# ProDoc_TP4056_2025-08-24.net
KiCad netlist of a schematic drawn in EasyEDA Pro
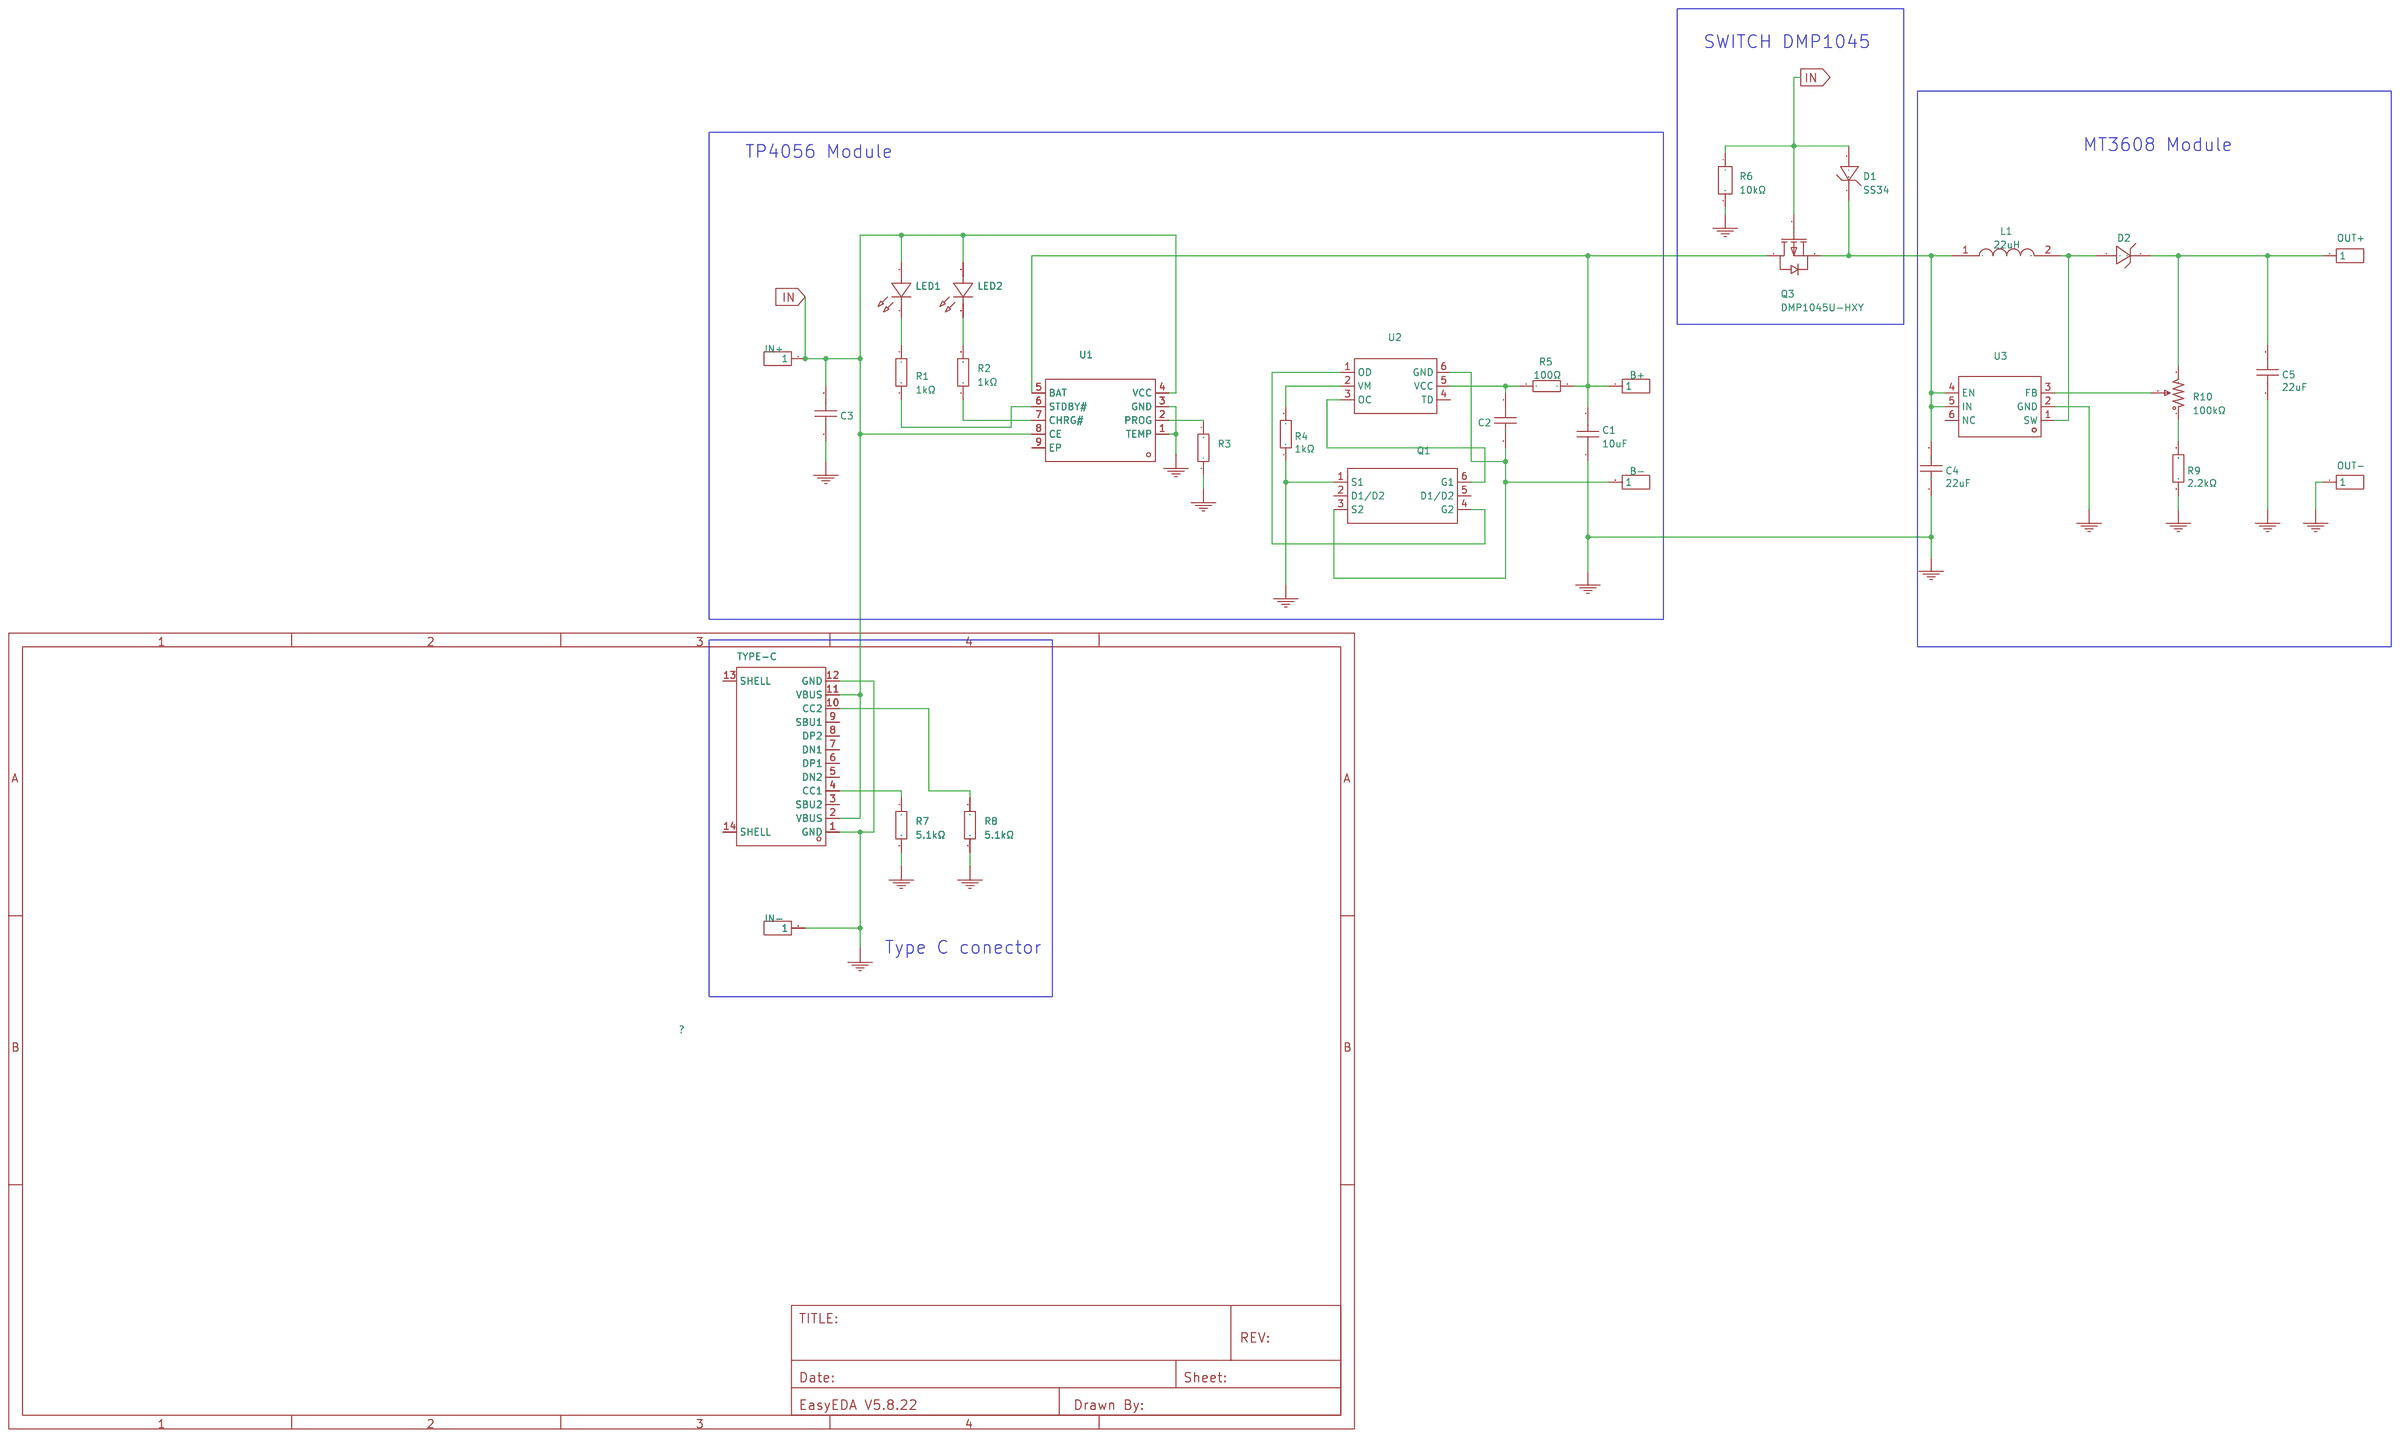
[diagram p0: schematic sheet]

(export (version "E")
  (design (tool "Eeschema 10.0.6"))
  (components
    (comp (ref "B+")
      (value "Header-Male-2.54_1x1")
      (footprint "easyedapro:HDR-1X1/2.54")
      (fields (field (name "Manufacturer") "ReliaPro"))
      (libsource (lib "") (part "Header-Male-2.54_1x1_1"))
    )
    (comp (ref "B-")
      (value "Header-Male-2.54_1x1")
      (footprint "easyedapro:HDR-1X1/2.54")
      (fields (field (name "Manufacturer") "ReliaPro"))
      (libsource (lib "") (part "Header-Male-2.54_1x1_1"))
    )
    (comp (ref "C1")
      (value "10uF")
      (footprint "easyedapro:C0603")
      (description "Capacitance:10uF Tolerance:±10% Tolerance:±10% Voltage Rating:- Temperature Coefficient:X5R")
      (fields (field (name "Manufacturer Part") "0603X106K100CT") (field (name "Manufacturer") "Walsin(华新科)"))
      (libsource (lib "easyedapro") (part "0603X106K100CT"))
    )
    (comp (ref "C2")
      (value "100nF")
      (footprint "easyedapro:C0603")
      (fields
        (field (name "Manufacturer Part") "CC0603KRX7R9BB104")
        (field (name "Manufacturer") "YAGEO(国巨)")
      )
      (libsource (lib "easyedapro") (part "CC0603KRX7R9BB104"))
    )
    (comp (ref "C3")
      (value "100nF")
      (footprint "easyedapro:C0603")
      (fields
        (field (name "Manufacturer Part") "CC0603KRX7R9BB104")
        (field (name "Manufacturer") "YAGEO(国巨)")
      )
      (libsource (lib "easyedapro") (part "CC0603KRX7R9BB104"))
    )
    (comp (ref "C4")
      (value "22uF")
      (footprint "easyedapro:C1206")
      (description "Capacitance:22uF Voltage Rating:25V Temperature Coefficient:-")
      (fields
        (field (name "Manufacturer Part") "C1206X6S226M250NT")
        (field (name "Manufacturer") "SANYEAR(叁叶源)")
      )
      (libsource (lib "easyedapro") (part "C1206X6S226M250NT"))
    )
    (comp (ref "C5")
      (value "22uF")
      (footprint "easyedapro:C1206")
      (description "Capacitance:22uF Voltage Rating:25V Temperature Coefficient:-")
      (fields
        (field (name "Manufacturer Part") "C1206X6S226M250NT")
        (field (name "Manufacturer") "SANYEAR(叁叶源)")
      )
      (libsource (lib "easyedapro") (part "C1206X6S226M250NT"))
    )
    (comp (ref "D1")
      (value "SS34")
      (footprint "easyedapro:SMB_L4.3-W3.6-LS5.3-RD")
      (fields (field (name "Manufacturer") "TECH PUBLIC(台舟)"))
      (libsource (lib "easyedapro") (part "SS34_C3040628"))
    )
    (comp (ref "D2")
      (value "SS34")
      (footprint "easyedapro:SMB_L4.3-W3.6-LS5.3-RD")
      (fields (field (name "Manufacturer") "TECH PUBLIC(台舟)"))
      (libsource (lib "easyedapro") (part "SS34_C3040628"))
    )
    (comp (ref "IN+")
      (value "Header-Male-2.54_1x1")
      (footprint "easyedapro:HDR-1X1/2.54")
      (fields (field (name "Manufacturer") "ReliaPro"))
      (libsource (lib "easyedapro") (part "Header-Male-2.54_1x1"))
    )
    (comp (ref "IN-")
      (value "Header-Male-2.54_1x1")
      (footprint "easyedapro:HDR-1X1/2.54")
      (fields (field (name "Manufacturer") "ReliaPro"))
      (libsource (lib "easyedapro") (part "Header-Male-2.54_1x1"))
    )
    (comp (ref "L1")
      (value "22uH")
      (footprint "easyedapro:IND-SMD_L7.8-W7.0_GCD75")
      (fields (field (name "Manufacturer Part") "CY75-22UH") (field (name "Manufacturer") "SHOU HAN(首韩)"))
      (libsource (lib "easyedapro") (part "CY75-22UH"))
    )
    (comp (ref "LED1")
      (value "A-SP192DGHC-C01-4T")
      (footprint "easyedapro:LED0603-FD")
      (fields (field (name "Manufacturer") "Amicc(欧密格光电)"))
      (libsource (lib "easyedapro") (part "A-SP192DGHC-C01-4T"))
    )
    (comp (ref "LED2")
      (value "XL-1608SURC-06")
      (footprint "easyedapro:LED0603-RD_RED")
      (fields (field (name "Manufacturer") "XINGLIGHT(成兴光)"))
      (libsource (lib "easyedapro") (part "XL-1608SURC-06"))
    )
    (comp (ref "OUT+")
      (value "Header-Male-2.54_1x1")
      (footprint "easyedapro:HDR-1X1/2.54")
      (fields (field (name "Manufacturer") "ReliaPro"))
      (libsource (lib "") (part "Header-Male-2.54_1x1_1"))
    )
    (comp (ref "OUT-")
      (value "Header-Male-2.54_1x1")
      (footprint "easyedapro:HDR-1X1/2.54")
      (fields (field (name "Manufacturer") "ReliaPro"))
      (libsource (lib "") (part "Header-Male-2.54_1x1_1"))
    )
    (comp (ref "Q1")
      (value "FS8205A")
      (footprint "easyedapro:SOT-23-6_L2.9-W1.6-P0.95-LS2.8-BR")
      (fields (field (name "Manufacturer") "FUXINSEMI(富芯森美)"))
      (libsource (lib "easyedapro") (part "FS8205A_C908265"))
    )
    (comp (ref "Q3")
      (value "DMP1045U-HXY")
      (footprint "easyedapro:SOT-23-3_L2.9-W1.5-P1.90-LS2.6-BR")
      (description "Type:1 piece P-channel Drain to Source Voltage:20V Current - Continuous Drain(Id):5A RDS(on):-")
      (fields (field (name "Manufacturer") "HXY MOSFET(华轩阳电子)"))
      (libsource (lib "easyedapro") (part "DMP1045U-HXY"))
    )
    (comp (ref "R1")
      (value "1kΩ")
      (footprint "easyedapro:R0603")
      (fields (field (name "Manufacturer Part") "RC0603FR-071KL") (field (name "Manufacturer") "YAGEO(国巨)"))
      (libsource (lib "easyedapro") (part "RC0603FR-071KL"))
    )
    (comp (ref "R2")
      (value "1kΩ")
      (footprint "easyedapro:R0603")
      (fields (field (name "Manufacturer Part") "RC0603FR-071KL") (field (name "Manufacturer") "YAGEO(国巨)"))
      (libsource (lib "easyedapro") (part "RC0603FR-071KL"))
    )
    (comp (ref "R3")
      (value "1.2kΩ")
      (footprint "easyedapro:R0603")
      (fields (field (name "Manufacturer Part") "RMC06031.2K5%N") (field (name "Manufacturer") "Tyohm(幸亚电阻)"))
      (libsource (lib "easyedapro") (part "RMC06031.2K5%N"))
    )
    (comp (ref "R4")
      (value "1kΩ")
      (footprint "easyedapro:R0603")
      (fields (field (name "Manufacturer Part") "RC0603FR-071KL") (field (name "Manufacturer") "YAGEO(国巨)"))
      (libsource (lib "easyedapro") (part "RC0603FR-071KL"))
    )
    (comp (ref "R5")
      (value "100Ω")
      (footprint "easyedapro:R0402")
      (fields
        (field (name "Manufacturer Part") "TR0402B100RQ1050Z")
        (field (name "Manufacturer") "EVER OHMS(天二科技)")
      )
      (libsource (lib "easyedapro") (part "TR0402B100RQ1050"))
    )
    (comp (ref "R6")
      (value "10kΩ")
      (footprint "easyedapro:R0603")
      (fields (field (name "Manufacturer Part") "FRC0603J103 TS") (field (name "Manufacturer") "FOJAN(富捷)"))
      (libsource (lib "easyedapro") (part "FRC0603J103TS"))
    )
    (comp (ref "R7")
      (value "5.1kΩ")
      (footprint "easyedapro:R0603")
      (fields
        (field (name "Manufacturer Part") "0603WAF5101T5E")
        (field (name "Manufacturer") "UNI-ROYAL(厚声)")
      )
      (libsource (lib "easyedapro") (part "0603WAF5101T5E"))
    )
    (comp (ref "R8")
      (value "5.1kΩ")
      (footprint "easyedapro:R0603")
      (fields
        (field (name "Manufacturer Part") "0603WAF5101T5E")
        (field (name "Manufacturer") "UNI-ROYAL(厚声)")
      )
      (libsource (lib "easyedapro") (part "0603WAF5101T5E"))
    )
    (comp (ref "R9")
      (value "2.2kΩ")
      (footprint "easyedapro:R0603")
      (fields
        (field (name "Manufacturer Part") "0603WAF2201T5E")
        (field (name "Manufacturer") "UNI-ROYAL(厚声)")
      )
      (libsource (lib "easyedapro") (part "0603WAF2201T5E"))
    )
    (comp (ref "R10")
      (value "100kΩ")
      (footprint "easyedapro:RES-ADJ-TH_3296P")
      (fields (field (name "Manufacturer Part") "3296P-1-104LF") (field (name "Manufacturer") "BOURNS"))
      (libsource (lib "easyedapro") (part "3296P-1-104LF"))
    )
    (comp (ref "TYPE-C")
      (value "TYPE-C 16PIN 2MD(073)")
      (footprint "easyedapro:USB-C-SMD_TYPE-C-6PIN-2MD-073")
      (fields (field (name "Manufacturer") "SHOU HAN(首韩)"))
      (libsource (lib "easyedapro") (part "TYPE-C 16PIN 2MD(073)"))
    )
    (comp (ref "U1")
      (value "TP4056")
      (footprint "easyedapro:ESOP-8_L4.9-W3.9-P1.27-LS6.0-BL-EP")
      (fields (field (name "Manufacturer") "TPOWER(天源)"))
      (libsource (lib "easyedapro") (part "TP4056_C382139"))
    )
    (comp (ref "U2")
      (value "DW01A")
      (footprint "easyedapro:SOT-23-6_L2.9-W1.6-P0.95-LS2.8-BL")
      (fields (field (name "Manufacturer") "PUOLOP(迪浦)"))
      (libsource (lib "easyedapro") (part "DW01A_C351410"))
    )
    (comp (ref "U3")
      (value "MT3608")
      (footprint "easyedapro:SOT-23-6_L2.9-W1.6-P0.95-LS2.8-BL")
      (fields (field (name "Manufacturer") "西安航天民芯"))
      (libsource (lib "easyedapro") (part "MT3608"))
    )
  )
  (nets
    (net (code "1") (name "GND") (class "Default")
      (node (ref "C1") (pin "1") (pinfunction "1_1") (pintype "unspecified"))
      (node (ref "C3") (pin "1") (pinfunction "1_1") (pintype "input"))
      (node (ref "C4") (pin "1") (pinfunction "1_1") (pintype "unspecified"))
      (node (ref "C5") (pin "1") (pinfunction "1_1") (pintype "unspecified"))
      (node (ref "IN-") (pin "1") (pinfunction "1_1") (pintype "input"))
      (node (ref "OUT-") (pin "1") (pinfunction "1_1") (pintype "input"))
      (node (ref "Q1") (pin "1") (pinfunction "S1_1") (pintype "unspecified"))
      (node (ref "R3") (pin "2") (pinfunction "2_2") (pintype "input"))
      (node (ref "R4") (pin "1") (pinfunction "1_1") (pintype "input"))
      (node (ref "R6") (pin "2") (pinfunction "2_2") (pintype "unspecified"))
      (node (ref "R7") (pin "2") (pinfunction "2_2") (pintype "input"))
      (node (ref "R8") (pin "2") (pinfunction "2_2") (pintype "input"))
      (node (ref "R9") (pin "1") (pinfunction "1_1") (pintype "input"))
      (node (ref "TYPE-C") (pin "1") (pinfunction "GND_1") (pintype "unspecified"))
      (node (ref "TYPE-C") (pin "12") (pinfunction "GND_12") (pintype "unspecified"))
      (node (ref "U1") (pin "1") (pinfunction "TEMP_1") (pintype "unspecified"))
      (node (ref "U1") (pin "3") (pinfunction "GND_3") (pintype "unspecified"))
      (node (ref "U3") (pin "2") (pinfunction "GND_2") (pintype "unspecified"))
    )
    (net (code "2") (name "IN") (class "Default")
      (node (ref "C3") (pin "2") (pinfunction "2_2") (pintype "input"))
      (node (ref "D1") (pin "2") (pinfunction "A_2") (pintype "unspecified"))
      (node (ref "IN+") (pin "1") (pinfunction "1_1") (pintype "input"))
      (node (ref "LED1") (pin "2") (pinfunction "A_2") (pintype "unspecified"))
      (node (ref "LED2") (pin "2") (pinfunction "A_2") (pintype "unspecified"))
      (node (ref "Q3") (pin "1") (pinfunction "G_1") (pintype "unspecified"))
      (node (ref "R6") (pin "1") (pinfunction "1_1") (pintype "unspecified"))
      (node (ref "TYPE-C") (pin "11") (pinfunction "VBUS_11") (pintype "unspecified"))
      (node (ref "TYPE-C") (pin "2") (pinfunction "VBUS_2") (pintype "unspecified"))
      (node (ref "U1") (pin "4") (pinfunction "VCC_4") (pintype "unspecified"))
      (node (ref "U1") (pin "8") (pinfunction "CE_8") (pintype "unspecified"))
    )
    (net (code "3") (name "Net-(D1-C)") (class "Default")
      (node (ref "C4") (pin "2") (pinfunction "2_2") (pintype "unspecified"))
      (node (ref "D1") (pin "1") (pinfunction "C_1") (pintype "unspecified"))
      (node (ref "L1") (pin "1") (pinfunction "1_1") (pintype "unspecified"))
      (node (ref "Q3") (pin "2") (pinfunction "S_2") (pintype "unspecified"))
      (node (ref "U3") (pin "4") (pinfunction "EN_4") (pintype "unspecified"))
      (node (ref "U3") (pin "5") (pinfunction "IN_5") (pintype "unspecified"))
    )
    (net (code "4") (name "Net-(D2-A)") (class "Default")
      (node (ref "D2") (pin "2") (pinfunction "A_2") (pintype "unspecified"))
      (node (ref "L1") (pin "2") (pinfunction "2_2") (pintype "unspecified"))
      (node (ref "U3") (pin "1") (pinfunction "SW_1") (pintype "unspecified"))
    )
    (net (code "5") (name "Net-(D2-C)") (class "Default")
      (node (ref "C5") (pin "2") (pinfunction "2_2") (pintype "unspecified"))
      (node (ref "D2") (pin "1") (pinfunction "C_1") (pintype "unspecified"))
      (node (ref "OUT+") (pin "1") (pinfunction "1_1") (pintype "input"))
      (node (ref "R10") (pin "3") (pinfunction "3_3") (pintype "unspecified"))
    )
    (net (code "6") (name "Net-(LED1-K)") (class "Default")
      (node (ref "LED1") (pin "1") (pinfunction "K_1") (pintype "unspecified"))
      (node (ref "R1") (pin "1") (pinfunction "1_1") (pintype "input"))
    )
    (net (code "7") (name "Net-(LED2-K)") (class "Default")
      (node (ref "LED2") (pin "1") (pinfunction "K_1") (pintype "unspecified"))
      (node (ref "R2") (pin "2") (pinfunction "2_2") (pintype "input"))
    )
    (net (code "8") (name "Net-(Q1-G1)") (class "Default")
      (node (ref "Q1") (pin "6") (pinfunction "G1_6") (pintype "unspecified"))
      (node (ref "U2") (pin "3") (pinfunction "OC_3") (pintype "unspecified"))
    )
    (net (code "9") (name "Net-(Q1-G2)") (class "Default")
      (node (ref "Q1") (pin "4") (pinfunction "G2_4") (pintype "unspecified"))
      (node (ref "U2") (pin "1") (pinfunction "OD_1") (pintype "unspecified"))
    )
    (net (code "10") (name "Net-(Q1-S2)") (class "Default")
      (node (ref "B-") (pin "1") (pinfunction "1_1") (pintype "input"))
      (node (ref "C2") (pin "2") (pinfunction "2_2") (pintype "input"))
      (node (ref "Q1") (pin "3") (pinfunction "S2_3") (pintype "unspecified"))
      (node (ref "U2") (pin "6") (pinfunction "GND_6") (pintype "unspecified"))
    )
    (net (code "11") (name "Net-(Q3-D)") (class "Default")
      (node (ref "B+") (pin "1") (pinfunction "1_1") (pintype "input"))
      (node (ref "C1") (pin "2") (pinfunction "2_2") (pintype "unspecified"))
      (node (ref "Q3") (pin "3") (pinfunction "D_3") (pintype "unspecified"))
      (node (ref "R5") (pin "2") (pinfunction "2_2") (pintype "input"))
      (node (ref "U1") (pin "5") (pinfunction "BAT_5") (pintype "unspecified"))
    )
    (net (code "12") (name "Net-(R10-Pad1)") (class "Default")
      (node (ref "R10") (pin "1") (pinfunction "1_1") (pintype "unspecified"))
      (node (ref "R9") (pin "2") (pinfunction "2_2") (pintype "input"))
    )
    (net (code "13") (name "Net-(TYPE-C-CC1)") (class "Default")
      (node (ref "R7") (pin "1") (pinfunction "1_1") (pintype "input"))
      (node (ref "TYPE-C") (pin "4") (pinfunction "CC1_4") (pintype "unspecified"))
    )
    (net (code "14") (name "Net-(TYPE-C-CC2)") (class "Default")
      (node (ref "R8") (pin "1") (pinfunction "1_1") (pintype "input"))
      (node (ref "TYPE-C") (pin "10") (pinfunction "CC2_10") (pintype "unspecified"))
    )
    (net (code "15") (name "Net-(U1-CHRG#)") (class "Default")
      (node (ref "R2") (pin "1") (pinfunction "1_1") (pintype "input"))
      (node (ref "U1") (pin "7") (pinfunction "CHRG#_7") (pintype "unspecified"))
    )
    (net (code "16") (name "Net-(U1-PROG)") (class "Default")
      (node (ref "R3") (pin "1") (pinfunction "1_1") (pintype "input"))
      (node (ref "U1") (pin "2") (pinfunction "PROG_2") (pintype "unspecified"))
    )
    (net (code "17") (name "Net-(U1-STDBY#)") (class "Default")
      (node (ref "R1") (pin "2") (pinfunction "2_2") (pintype "input"))
      (node (ref "U1") (pin "6") (pinfunction "STDBY#_6") (pintype "unspecified"))
    )
    (net (code "18") (name "Net-(U2-VCC)") (class "Default")
      (node (ref "C2") (pin "1") (pinfunction "1_1") (pintype "input"))
      (node (ref "R5") (pin "1") (pinfunction "1_1") (pintype "input"))
      (node (ref "U2") (pin "5") (pinfunction "VCC_5") (pintype "unspecified"))
    )
    (net (code "19") (name "Net-(U2-VM)") (class "Default")
      (node (ref "R4") (pin "2") (pinfunction "2_2") (pintype "input"))
      (node (ref "U2") (pin "2") (pinfunction "VM_2") (pintype "unspecified"))
    )
    (net (code "20") (name "Net-(U3-FB)") (class "Default")
      (node (ref "R10") (pin "2") (pinfunction "2_2") (pintype "unspecified"))
      (node (ref "U3") (pin "3") (pinfunction "FB_3") (pintype "unspecified"))
    )
    (net (code "21") (name "unconnected-(Q1-D1{slash}D2-Pad2)") (class "Default")
      (node (ref "Q1") (pin "2") (pinfunction "D1/D2_2") (pintype "unspecified"))
    )
    (net (code "22") (name "unconnected-(Q1-D1{slash}D2-Pad5)") (class "Default")
      (node (ref "Q1") (pin "5") (pinfunction "D1/D2_5") (pintype "unspecified"))
    )
    (net (code "23") (name "unconnected-(TYPE-C-DN1-Pad7)") (class "Default")
      (node (ref "TYPE-C") (pin "7") (pinfunction "DN1_7") (pintype "unspecified"))
    )
    (net (code "24") (name "unconnected-(TYPE-C-DN2-Pad5)") (class "Default")
      (node (ref "TYPE-C") (pin "5") (pinfunction "DN2_5") (pintype "unspecified"))
    )
    (net (code "25") (name "unconnected-(TYPE-C-DP1-Pad6)") (class "Default")
      (node (ref "TYPE-C") (pin "6") (pinfunction "DP1_6") (pintype "unspecified"))
    )
    (net (code "26") (name "unconnected-(TYPE-C-DP2-Pad8)") (class "Default")
      (node (ref "TYPE-C") (pin "8") (pinfunction "DP2_8") (pintype "unspecified"))
    )
    (net (code "27") (name "unconnected-(TYPE-C-SBU1-Pad9)") (class "Default")
      (node (ref "TYPE-C") (pin "9") (pinfunction "SBU1_9") (pintype "unspecified"))
    )
    (net (code "28") (name "unconnected-(TYPE-C-SBU2-Pad3)") (class "Default")
      (node (ref "TYPE-C") (pin "3") (pinfunction "SBU2_3") (pintype "unspecified"))
    )
    (net (code "29") (name "unconnected-(TYPE-C-SHELL-Pad13)") (class "Default")
      (node (ref "TYPE-C") (pin "13") (pinfunction "SHELL_13") (pintype "unspecified"))
    )
    (net (code "30") (name "unconnected-(TYPE-C-SHELL-Pad14)") (class "Default")
      (node (ref "TYPE-C") (pin "14") (pinfunction "SHELL_14") (pintype "unspecified"))
    )
    (net (code "31") (name "unconnected-(U1-EP-Pad9)") (class "Default")
      (node (ref "U1") (pin "9") (pinfunction "EP_9") (pintype "unspecified"))
    )
    (net (code "32") (name "unconnected-(U2-TD-Pad4)") (class "Default")
      (node (ref "U2") (pin "4") (pinfunction "TD_4") (pintype "unspecified"))
    )
    (net (code "33") (name "unconnected-(U3-NC-Pad6)") (class "Default")
      (node (ref "U3") (pin "6") (pinfunction "NC_6") (pintype "unspecified"))
    )
  )
)
